# RFID_PCB_Antenna_Interfaces.net
KiCad netlist of a schematic drawn in Altium Designer
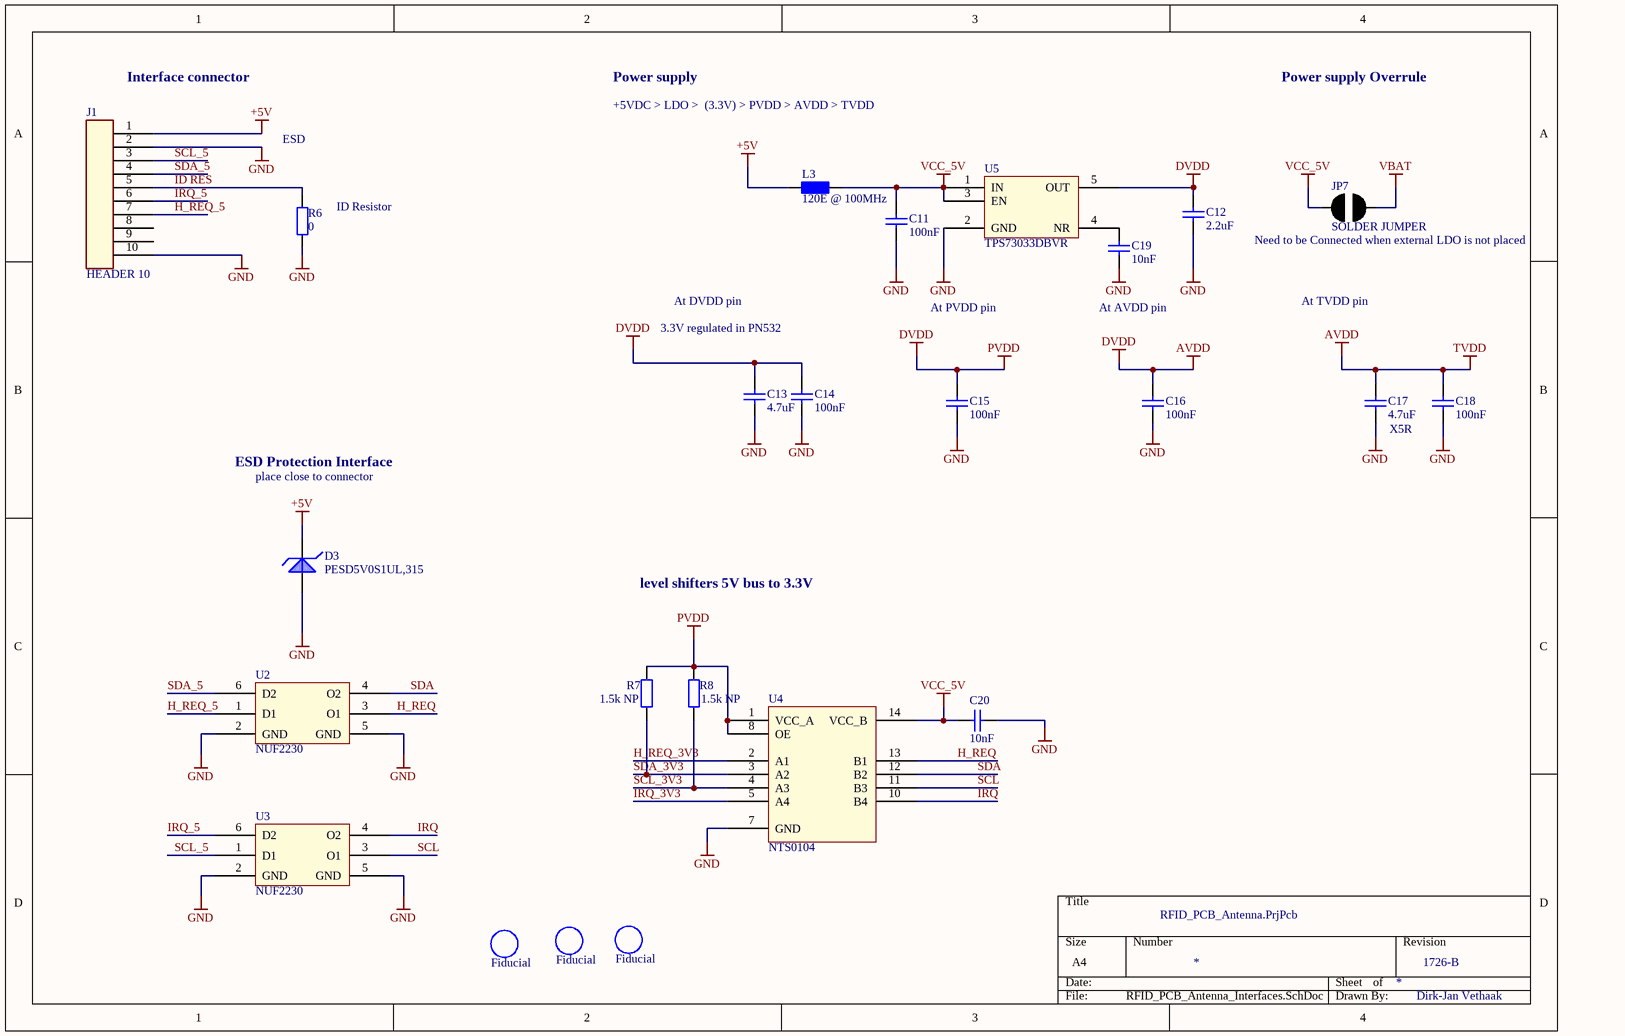
[diagram p0: RFID_PCB_Antenna_Interfaces.SchDoc]

(export (version "E")
  (design (tool "Eeschema 10.0.6"))
  (components
    (comp (ref "C11")
      (value "100nF")
      (footprint "cap0402")
      (description "C0402")
      (fields
        (field (name "MANUFACTURER") "Vishay / Vitramon")
        (field (name "MANUFACTURER PART NUMBER") "VJ0402G104KXQCW1BC")
      )
      (libsource (lib "RFIDboard") (part "C0402"))
    )
    (comp (ref "C12")
      (value "2.2uF")
      (footprint "cap0402")
      (description "C0402")
      (fields
        (field (name "MANUFACTURER") "Murata Electronics")
        (field (name "MANUFACTURER PART NUMBER") "GRM155R61A225KE95D")
      )
      (libsource (lib "RFIDboard") (part "C0402"))
    )
    (comp (ref "C13")
      (value "4.7uF")
      (footprint "cap0402")
      (description "C0402")
      (fields
        (field (name "MANUFACTURER") "Murata Electronics")
        (field (name "MANUFACTURER PART NUMBER") "GRM155R60J475ME87D")
      )
      (libsource (lib "RFIDboard") (part "C0402"))
    )
    (comp (ref "C14")
      (value "100nF")
      (footprint "cap0402")
      (description "C0402")
      (fields
        (field (name "MANUFACTURER") "Vishay / Vitramon")
        (field (name "MANUFACTURER PART NUMBER") "VJ0402G104KXQCW1BC")
      )
      (libsource (lib "RFIDboard") (part "C0402"))
    )
    (comp (ref "C15")
      (value "100nF")
      (footprint "cap0402")
      (description "C0402")
      (fields
        (field (name "MANUFACTURER") "Vishay / Vitramon")
        (field (name "MANUFACTURER PART NUMBER") "VJ0402G104KXQCW1BC")
      )
      (libsource (lib "RFIDboard") (part "C0402"))
    )
    (comp (ref "C16")
      (value "100nF")
      (footprint "cap0402")
      (description "C0402")
      (fields
        (field (name "MANUFACTURER") "Vishay / Vitramon")
        (field (name "MANUFACTURER PART NUMBER") "VJ0402G104KXQCW1BC")
      )
      (libsource (lib "RFIDboard") (part "C0402"))
    )
    (comp (ref "C17")
      (value "4.7uF")
      (footprint "cap0402")
      (description "C0402")
      (fields
        (field (name "MANUFACTURER") "Murata Electronics")
        (field (name "MANUFACTURER PART NUMBER") "GRM155R60J475ME87D")
      )
      (libsource (lib "RFIDboard") (part "C0402"))
    )
    (comp (ref "C18")
      (value "100nF")
      (footprint "cap0402")
      (description "C0402")
      (fields
        (field (name "MANUFACTURER") "Vishay / Vitramon")
        (field (name "MANUFACTURER PART NUMBER") "VJ0402G104KXQCW1BC")
      )
      (libsource (lib "RFIDboard") (part "C0402"))
    )
    (comp (ref "C19")
      (value "10nF")
      (footprint "cap0402")
      (description "C0402")
      (fields
        (field (name "MANUFACTURER") "Vishay / Vitramon")
        (field (name "MANUFACTURER PART NUMBER") "VJ0402Y103KXJCW1BC")
      )
      (libsource (lib "RFIDboard") (part "C0402"))
    )
    (comp (ref "C20")
      (value "10nF")
      (footprint "cap0402")
      (description "C0402")
      (fields
        (field (name "MANUFACTURER") "Vishay / Vitramon")
        (field (name "MANUFACTURER PART NUMBER") "VJ0402Y103KXJCW1BC")
      )
      (libsource (lib "RFIDboard") (part "C0402"))
    )
    (comp (ref "D3")
      (value "PESD5V0S1UL")
      (footprint "DFN65P100X50-2N")
      (description "TVS DIODE 5VWM 20VC SOD882")
      (fields
        (field (name "MANUFACTURER") "NXP Semiconductors")
        (field (name "MANUFACTURER PART NUMBER") "PESD5V0S1UL,315")
      )
      (libsource (lib "RFIDboard") (part "TVS Diode"))
    )
    (comp (ref "Fid1")
      (value "Fiducial")
      (footprint "Fiducial")
      (libsource (lib "CopyUltimainboard") (part "Fiducial"))
    )
    (comp (ref "Fid2")
      (value "Fiducial")
      (footprint "Fiducial")
      (libsource (lib "CopyUltimainboard") (part "Fiducial"))
    )
    (comp (ref "Fid3")
      (value "Fiducial")
      (footprint "Fiducial")
      (libsource (lib "CopyUltimainboard") (part "Fiducial"))
    )
    (comp (ref "J1")
      (value "HEADER 10")
      (footprint "HEADER-2X5P-ST-2")
      (description "B10B-PHDSS(LF)(SN)")
      (fields (field (name "MANUFACTURER") "JST Sales America Inc."))
      (libsource (lib "RFIDboard") (part "HEADER 10"))
    )
    (comp (ref "JP7")
      (value "SOLDER JUMPER")
      (footprint "Jumper Solder 0402")
      (libsource (lib "RFIDboard") (part "JUMPER 2 SOLDER"))
    )
    (comp (ref "L3")
      (value "120E @ 100MHz")
      (footprint "R0603")
      (description "FERRIET BLM18PG121SN1D 0603 MURATA")
      (fields (field (name "MFG") "Murata") (field (name "MANUFACTURER") "Murata Electronics North America"))
      (libsource (lib "RFIDboard") (part "Ferriet Bead 120E"))
    )
    (comp (ref "R6")
      (value "0")
      (footprint "RESC1105X04N")
      (description "R0402")
      (fields
        (field (name "MANUFACTURER") "VISHAY")
        (field (name "MANUFACTURER PART NUMBER") "CRCW04020000Z0ED")
      )
      (libsource (lib "RFIDboard") (part "R0402"))
    )
    (comp (ref "R7")
      (value "1.5k NP")
      (footprint "RESC1105X04N")
      (description "R0402")
      (fields
        (field (name "MANUFACTURER") "Vishay Dale")
        (field (name "MANUFACTURER PART NUMBER") "CRCW04021K50JNED")
      )
      (libsource (lib "RFIDboard") (part "R0402"))
    )
    (comp (ref "R8")
      (value "1.5k NP")
      (footprint "RESC1105X04N")
      (description "R0402")
      (fields
        (field (name "MANUFACTURER") "Vishay Dale")
        (field (name "MANUFACTURER PART NUMBER") "CRCW04021K50JNED")
      )
      (libsource (lib "RFIDboard") (part "R0402"))
    )
    (comp (ref "U2")
      (value "NUF2230")
      (footprint "SOTFL50P160X60-6N")
      (description "NUF2230XV6T1G")
      (fields (field (name "MFG") "ON Semiconductor"))
      (libsource (lib "RFIDboard") (part "NUF2230"))
    )
    (comp (ref "U3")
      (value "NUF2230")
      (footprint "SOTFL50P160X60-6N")
      (description "NUF2230XV6T1G")
      (fields (field (name "MFG") "ON Semiconductor"))
      (libsource (lib "RFIDboard") (part "NUF2230"))
    )
    (comp (ref "U4")
      (value "NTS0104")
      (footprint "QFN50P300X250X100_HS-15N")
      (description "NTS0104BQ,115, DHVQFN14")
      (fields
        (field (name "MANUFACTURER") "NXP Semiconductors")
        (field (name "MANUFACTURER PART NUMBER") "NTS0104BQ,115")
      )
      (libsource (lib "RFIDboard") (part "NTS0104"))
    )
    (comp (ref "U5")
      (value "TPS73033DBVR")
      (footprint "SOT95P280X145-5N")
      (description "LDO 3.3V")
      (fields (field (name "MANUFACTURER") "Texas Instruments"))
      (libsource (lib "RFIDboard") (part "TPS73033DBVR"))
    )
  )
  (nets
    (net (code "1") (name "+5V") (class "Default")
      (node (ref "D3") (pin "1") (pinfunction "K_1") (pintype "passive"))
      (node (ref "J1") (pin "1") (pinfunction "1_1") (pintype "passive"))
      (node (ref "L3") (pin "1") (pinfunction "1_1") (pintype "passive"))
    )
    (net (code "2") (name "/H_REQ") (class "Default")
      (node (ref "U2") (pin "3") (pinfunction "O1_3") (pintype "passive"))
      (node (ref "U4") (pin "13") (pinfunction "B1_13") (pintype "passive"))
    )
    (net (code "3") (name "/H_REQ_3V3") (class "Default")
      (node (ref "U4") (pin "2") (pinfunction "A1_2") (pintype "passive"))
    )
    (net (code "4") (name "/H_REQ_5") (class "Default")
      (node (ref "J1") (pin "7") (pinfunction "7_7") (pintype "passive"))
      (node (ref "U2") (pin "1") (pinfunction "D1_1") (pintype "passive"))
    )
    (net (code "5") (name "/ID RES") (class "Default")
      (node (ref "J1") (pin "5") (pinfunction "5_5") (pintype "passive"))
      (node (ref "R6") (pin "2") (pinfunction "2_2") (pintype "passive"))
    )
    (net (code "6") (name "/IRQ") (class "Default")
      (node (ref "U3") (pin "4") (pinfunction "O2_4") (pintype "passive"))
      (node (ref "U4") (pin "10") (pinfunction "B4_10") (pintype "passive"))
    )
    (net (code "7") (name "/IRQ_3V3") (class "Default")
      (node (ref "U4") (pin "5") (pinfunction "A4_5") (pintype "passive"))
    )
    (net (code "8") (name "/IRQ_5") (class "Default")
      (node (ref "J1") (pin "6") (pinfunction "6_6") (pintype "passive"))
      (node (ref "U3") (pin "6") (pinfunction "D2_6") (pintype "passive"))
    )
    (net (code "9") (name "/SCL") (class "Default")
      (node (ref "U3") (pin "3") (pinfunction "O1_3") (pintype "passive"))
      (node (ref "U4") (pin "11") (pinfunction "B3_11") (pintype "passive"))
    )
    (net (code "10") (name "/SCL_3V3") (class "Default")
      (node (ref "R8") (pin "1") (pinfunction "1_1") (pintype "passive"))
      (node (ref "U4") (pin "4") (pinfunction "A3_4") (pintype "passive"))
    )
    (net (code "11") (name "/SCL_5") (class "Default")
      (node (ref "J1") (pin "3") (pinfunction "3_3") (pintype "passive"))
      (node (ref "U3") (pin "1") (pinfunction "D1_1") (pintype "passive"))
    )
    (net (code "12") (name "/SDA") (class "Default")
      (node (ref "U2") (pin "4") (pinfunction "O2_4") (pintype "passive"))
      (node (ref "U4") (pin "12") (pinfunction "B2_12") (pintype "passive"))
    )
    (net (code "13") (name "/SDA_3V3") (class "Default")
      (node (ref "R7") (pin "1") (pinfunction "1_1") (pintype "passive"))
      (node (ref "U4") (pin "3") (pinfunction "A2_3") (pintype "passive"))
    )
    (net (code "14") (name "/SDA_5") (class "Default")
      (node (ref "J1") (pin "4") (pinfunction "4_4") (pintype "passive"))
      (node (ref "U2") (pin "6") (pinfunction "D2_6") (pintype "passive"))
    )
    (net (code "15") (name "AVDD") (class "Default")
      (node (ref "C12") (pin "2") (pinfunction "2_2") (pintype "passive"))
      (node (ref "C13") (pin "2") (pinfunction "2_2") (pintype "passive"))
      (node (ref "C14") (pin "2") (pinfunction "2_2") (pintype "passive"))
      (node (ref "C15") (pin "2") (pinfunction "2_2") (pintype "passive"))
      (node (ref "C16") (pin "2") (pinfunction "2_2") (pintype "passive"))
      (node (ref "C17") (pin "2") (pinfunction "2_2") (pintype "passive"))
      (node (ref "C18") (pin "2") (pinfunction "2_2") (pintype "passive"))
      (node (ref "R7") (pin "2") (pinfunction "2_2") (pintype "passive"))
      (node (ref "R8") (pin "2") (pinfunction "2_2") (pintype "passive"))
      (node (ref "U4") (pin "1") (pinfunction "VCC_A_1") (pintype "passive"))
      (node (ref "U4") (pin "8") (pinfunction "OE_8") (pintype "passive"))
      (node (ref "U5") (pin "5") (pinfunction "OUT_5") (pintype "passive"))
    )
    (net (code "16") (name "GND") (class "Default")
      (node (ref "C11") (pin "1") (pinfunction "1_1") (pintype "passive"))
      (node (ref "C12") (pin "1") (pinfunction "1_1") (pintype "passive"))
      (node (ref "C13") (pin "1") (pinfunction "1_1") (pintype "passive"))
      (node (ref "C14") (pin "1") (pinfunction "1_1") (pintype "passive"))
      (node (ref "C15") (pin "1") (pinfunction "1_1") (pintype "passive"))
      (node (ref "C16") (pin "1") (pinfunction "1_1") (pintype "passive"))
      (node (ref "C17") (pin "1") (pinfunction "1_1") (pintype "passive"))
      (node (ref "C18") (pin "1") (pinfunction "1_1") (pintype "passive"))
      (node (ref "C19") (pin "2") (pinfunction "2_2") (pintype "passive"))
      (node (ref "C20") (pin "1") (pinfunction "1_1") (pintype "passive"))
      (node (ref "D3") (pin "2") (pinfunction "A_2") (pintype "passive"))
      (node (ref "J1") (pin "10") (pinfunction "10_10") (pintype "passive"))
      (node (ref "J1") (pin "2") (pinfunction "2_2") (pintype "passive"))
      (node (ref "R6") (pin "1") (pinfunction "1_1") (pintype "passive"))
      (node (ref "U2") (pin "2") (pinfunction "GND_2") (pintype "passive"))
      (node (ref "U2") (pin "5") (pinfunction "GND_5") (pintype "passive"))
      (node (ref "U3") (pin "2") (pinfunction "GND_2") (pintype "passive"))
      (node (ref "U3") (pin "5") (pinfunction "GND_5") (pintype "passive"))
      (node (ref "U4") (pin "7") (pinfunction "GND_7") (pintype "passive"))
      (node (ref "U5") (pin "2") (pinfunction "GND_2") (pintype "passive"))
    )
    (net (code "17") (name "Net-(U5-NR)") (class "Default")
      (node (ref "C19") (pin "1") (pinfunction "1_1") (pintype "passive"))
      (node (ref "U5") (pin "4") (pinfunction "NR_4") (pintype "passive"))
    )
    (net (code "18") (name "VBAT") (class "Default")
      (node (ref "JP7") (pin "2") (pinfunction "2_2") (pintype "passive"))
    )
    (net (code "19") (name "VCC_5V") (class "Default")
      (node (ref "C11") (pin "2") (pinfunction "2_2") (pintype "passive"))
      (node (ref "C20") (pin "2") (pinfunction "2_2") (pintype "passive"))
      (node (ref "JP7") (pin "1") (pinfunction "1_1") (pintype "passive"))
      (node (ref "L3") (pin "2") (pinfunction "2_2") (pintype "passive"))
      (node (ref "U4") (pin "14") (pinfunction "VCC_B_14") (pintype "passive"))
      (node (ref "U5") (pin "1") (pinfunction "IN_1") (pintype "passive"))
      (node (ref "U5") (pin "3") (pinfunction "EN_3") (pintype "passive"))
    )
    (net (code "20") (name "unconnected-(J1-Pad8)") (class "Default")
      (node (ref "J1") (pin "8") (pinfunction "8_8") (pintype "passive"))
    )
    (net (code "21") (name "unconnected-(J1-Pad9)") (class "Default")
      (node (ref "J1") (pin "9") (pinfunction "9_9") (pintype "passive"))
    )
    (net (code "22") (name "unconnected-(U4-NC-Pad6)") (class "Default")
      (node (ref "U4") (pin "6") (pinfunction "NC_6") (pintype "passive"))
    )
    (net (code "23") (name "unconnected-(U4-NC-Pad9)") (class "Default")
      (node (ref "U4") (pin "9") (pinfunction "NC_9") (pintype "passive"))
    )
  )
)
